# MCU.net
KiCad netlist of a schematic drawn in Altium Designer
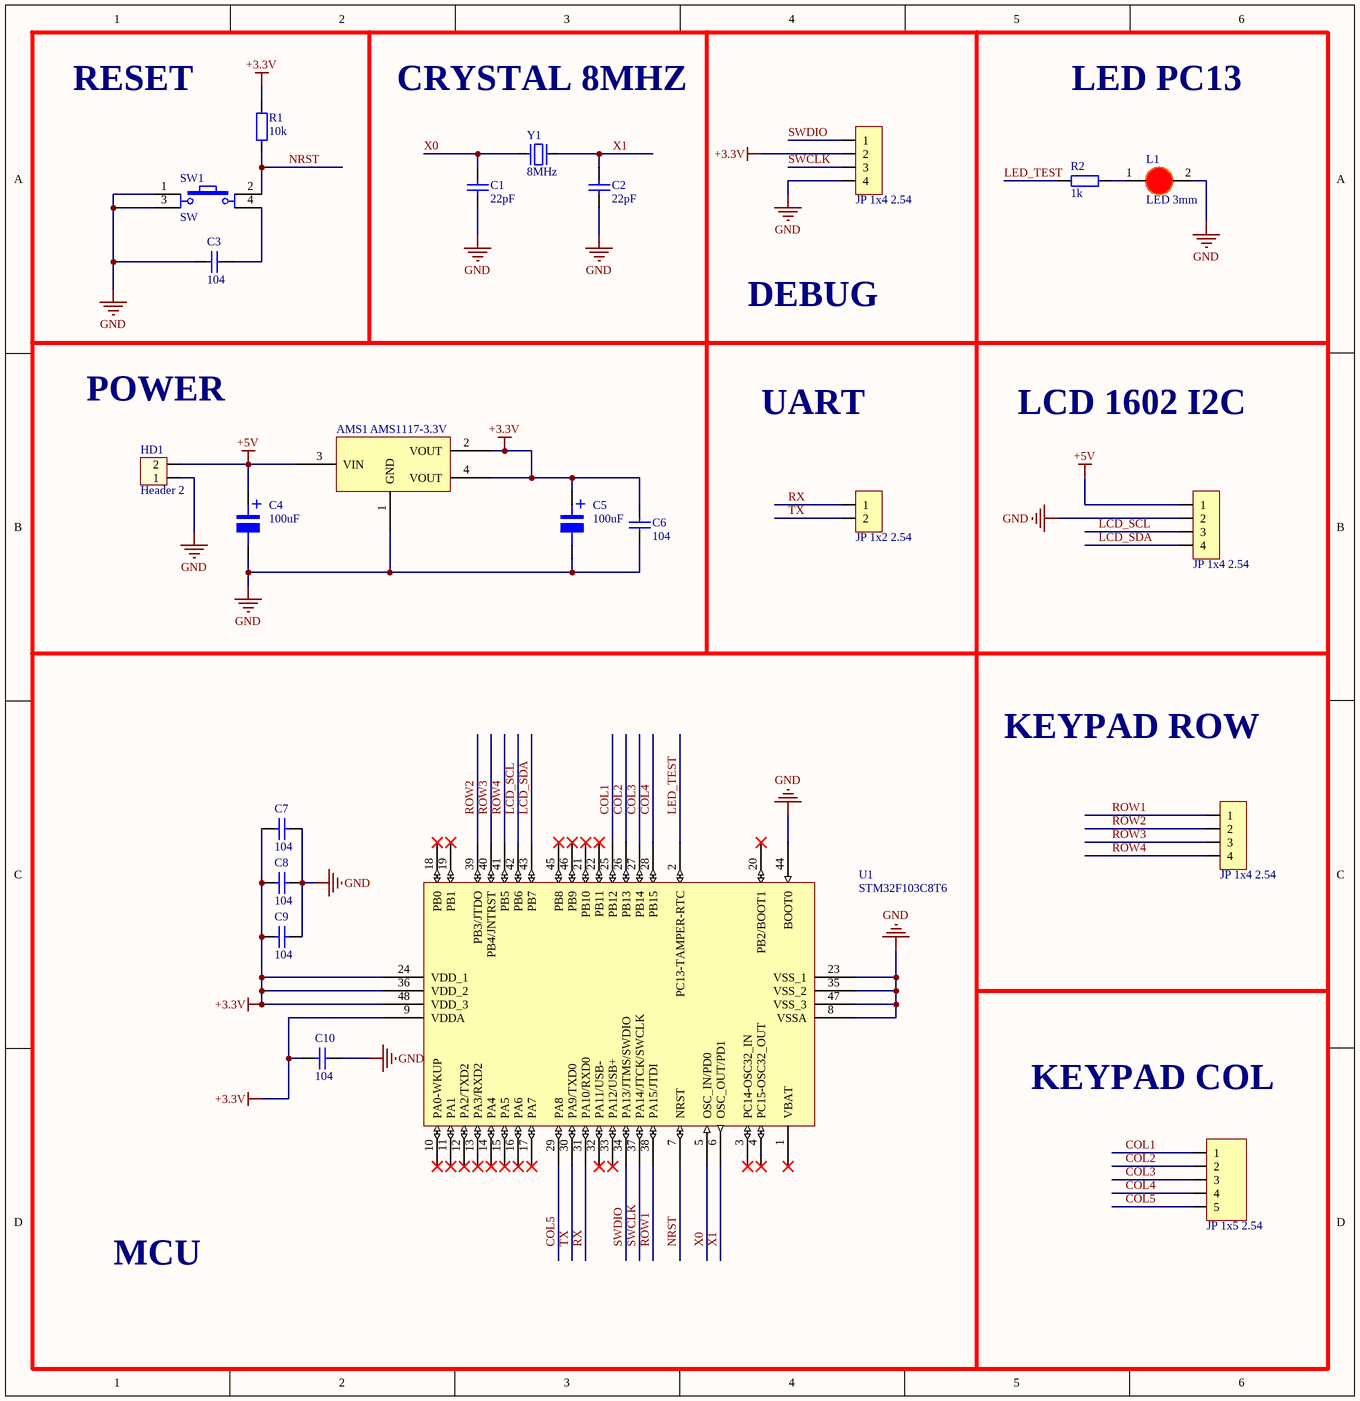
[diagram p0: MCU.SchDoc]

(export (version "E")
  (design (tool "Eeschema 10.0.6"))
  (components
    (comp (ref "AMS1")
      (value "AMS1117-3.3V")
      (footprint "SOT223")
      (description "Dán")
      (libsource (lib "Altium_Lib_by_KhueNguyenCreator") (part "AMS1117 SMD"))
    )
    (comp (ref "C1")
      (value "22pF")
      (footprint "tu 1206")
      (description "Dán")
      (libsource (lib "Altium_Lib_by_KhueNguyenCreator") (part "Tu 1206 22pF 50V 10%"))
    )
    (comp (ref "C2")
      (value "22pF")
      (footprint "tu 1206")
      (description "Dán")
      (libsource (lib "Altium_Lib_by_KhueNguyenCreator") (part "Tu 1206 22pF 50V 10%"))
    )
    (comp (ref "C3")
      (value "104")
      (footprint "tu 1206")
      (description "Dán")
      (libsource (lib "Altium_Lib_by_KhueNguyenCreator") (part "Tu 1206 104 50V 20%"))
    )
    (comp (ref "C4")
      (value "100uF")
      (footprint "tu nhom 6.3 (d)")
      (description "Dán")
      (libsource (lib "Altium_Lib_by_KhueNguyenCreator") (part "Tu Nhom 100uF 16V"))
    )
    (comp (ref "C5")
      (value "100uF")
      (footprint "tu nhom 6.3 (d)")
      (description "Dán")
      (libsource (lib "Altium_Lib_by_KhueNguyenCreator") (part "Tu Nhom 100uF 16V"))
    )
    (comp (ref "C6")
      (value "104")
      (footprint "tu 1206")
      (description "Dán")
      (libsource (lib "Altium_Lib_by_KhueNguyenCreator") (part "Tu 1206 104 50V 20%"))
    )
    (comp (ref "C7")
      (value "104")
      (footprint "tu 1206")
      (description "Dán")
      (libsource (lib "Altium_Lib_by_KhueNguyenCreator") (part "Tu 1206 104 50V 20%"))
    )
    (comp (ref "C8")
      (value "104")
      (footprint "tu 1206")
      (description "Dán")
      (libsource (lib "Altium_Lib_by_KhueNguyenCreator") (part "Tu 1206 104 50V 20%"))
    )
    (comp (ref "C9")
      (value "104")
      (footprint "tu 1206")
      (description "Dán")
      (libsource (lib "Altium_Lib_by_KhueNguyenCreator") (part "Tu 1206 104 50V 20%"))
    )
    (comp (ref "C10")
      (value "104")
      (footprint "tu 1206")
      (description "Dán")
      (libsource (lib "Altium_Lib_by_KhueNguyenCreator") (part "Tu 1206 104 50V 20%"))
    )
    (comp (ref "HD1")
      (value "Header 2")
      (footprint "HED2")
      (description "Header 2 (Green)")
      (libsource (lib "syhaunguyen") (part "Hed2"))
    )
    (comp (ref "JP1")
      (value "JP 1x4 2.54")
      (footprint "JP 1x4 DT")
      (description "Cắm")
      (libsource (lib "Altium_Lib_by_KhueNguyenCreator") (part "JP 1x4 2.54 Duc Thang"))
    )
    (comp (ref "JP2")
      (value "JP 1x2 2.54")
      (footprint "JP 1x2 DT")
      (description "Cắm")
      (libsource (lib "Altium_Lib_by_KhueNguyenCreator") (part "JP 1x2 2.54 Duc Thang"))
    )
    (comp (ref "JP3")
      (value "JP 1x4 2.54")
      (footprint "JP 1x4 DT")
      (description "Cắm")
      (libsource (lib "Altium_Lib_by_KhueNguyenCreator") (part "JP 1x4 2.54 Duc Thang"))
    )
    (comp (ref "JP4")
      (value "JP 1x4 2.54")
      (footprint "JP 1x4 DT")
      (description "Cắm")
      (libsource (lib "Altium_Lib_by_KhueNguyenCreator") (part "JP 1x4 2.54 Duc Thang"))
    )
    (comp (ref "JP5")
      (value "JP 1x5 2.54")
      (footprint "JP 1x5 DT")
      (description "Cắm")
      (libsource (lib "Altium_Lib_by_KhueNguyenCreator") (part "JP 1x5 2.54 Duc Thang"))
    )
    (comp (ref "L1")
      (value "LED 3mm")
      (footprint "LED-3MM-RED")
      (description "Cắm")
      (libsource (lib "Altium_Lib_by_KhueNguyenCreator") (part "LED 3mm Do"))
    )
    (comp (ref "R1")
      (value "10k")
      (footprint "tro smd 1206")
      (description "Dán")
      (libsource (lib "Altium_Lib_by_KhueNguyenCreator") (part "Tro 1206 1% 10k"))
    )
    (comp (ref "R2")
      (value "1k")
      (footprint "tro smd 1206")
      (description "Dán")
      (libsource (lib "Altium_Lib_by_KhueNguyenCreator") (part "Tro 1206 1% 1k"))
    )
    (comp (ref "SW1")
      (value "SW")
      (footprint "SW4")
      (description "Switch button 4 pin")
      (libsource (lib "syhaunguyen") (part "SW4"))
    )
    (comp (ref "U1")
      (value "STM32F103C8T6")
      (footprint "LQFP48")
      (fields (field (name "PUBLISHER") "Altium Limited"))
      (libsource (lib "Electronic4u") (part "STM32F103C8T6"))
    )
    (comp (ref "Y1")
      (value "8MHz")
      (footprint "Thach Anh 2 chan SMD")
      (description "Crystal For all Crystal 2pin.")
      (libsource (lib "Altium_Lib_by_KhueNguyenCreator") (part "Thach Anh 2 chan SMD"))
    )
  )
  (nets
    (net (code "1") (name "+3.3V") (class "Default")
      (node (ref "AMS1") (pin "2") (pinfunction "VOUT_2") (pintype "passive"))
      (node (ref "AMS1") (pin "4") (pinfunction "VOUT_4") (pintype "passive"))
      (node (ref "C10") (pin "1") (pinfunction "1_1") (pintype "passive"))
      (node (ref "C5") (pin "1") (pinfunction "1_1") (pintype "passive"))
      (node (ref "C6") (pin "1") (pinfunction "1_1") (pintype "passive"))
      (node (ref "C7") (pin "1") (pinfunction "1_1") (pintype "passive"))
      (node (ref "C8") (pin "1") (pinfunction "1_1") (pintype "passive"))
      (node (ref "C9") (pin "1") (pinfunction "1_1") (pintype "passive"))
      (node (ref "JP1") (pin "2") (pinfunction "2_2") (pintype "passive"))
      (node (ref "R1") (pin "2") (pinfunction "2_2") (pintype "passive"))
      (node (ref "U1") (pin "24") (pinfunction "VDD_1_24") (pintype "power_in"))
      (node (ref "U1") (pin "36") (pinfunction "VDD_2_36") (pintype "power_in"))
      (node (ref "U1") (pin "48") (pinfunction "VDD_3_48") (pintype "power_in"))
      (node (ref "U1") (pin "9") (pinfunction "VDDA_9") (pintype "power_in"))
    )
    (net (code "2") (name "+5V") (class "Default")
      (node (ref "AMS1") (pin "3") (pinfunction "VIN_3") (pintype "passive"))
      (node (ref "C4") (pin "1") (pinfunction "1_1") (pintype "passive"))
      (node (ref "HD1") (pin "2") (pinfunction "2_2") (pintype "passive"))
      (node (ref "JP3") (pin "1") (pinfunction "1_1") (pintype "passive"))
    )
    (net (code "3") (name "/COL1") (class "Default")
      (node (ref "JP5") (pin "1") (pinfunction "1_1") (pintype "passive"))
      (node (ref "U1") (pin "25") (pinfunction "PB12_25") (pintype "bidirectional"))
    )
    (net (code "4") (name "/COL2") (class "Default")
      (node (ref "JP5") (pin "2") (pinfunction "2_2") (pintype "passive"))
      (node (ref "U1") (pin "26") (pinfunction "PB13_26") (pintype "bidirectional"))
    )
    (net (code "5") (name "/COL3") (class "Default")
      (node (ref "JP5") (pin "3") (pinfunction "3_3") (pintype "passive"))
      (node (ref "U1") (pin "27") (pinfunction "PB14_27") (pintype "bidirectional"))
    )
    (net (code "6") (name "/COL4") (class "Default")
      (node (ref "JP5") (pin "4") (pinfunction "4_4") (pintype "passive"))
      (node (ref "U1") (pin "28") (pinfunction "PB15_28") (pintype "bidirectional"))
    )
    (net (code "7") (name "/COL5") (class "Default")
      (node (ref "JP5") (pin "5") (pinfunction "5_5") (pintype "passive"))
      (node (ref "U1") (pin "29") (pinfunction "PA8_29") (pintype "bidirectional"))
    )
    (net (code "8") (name "/LCD_SCL") (class "Default")
      (node (ref "JP3") (pin "3") (pinfunction "3_3") (pintype "passive"))
      (node (ref "U1") (pin "42") (pinfunction "PB6_42") (pintype "bidirectional"))
    )
    (net (code "9") (name "/LCD_SDA") (class "Default")
      (node (ref "JP3") (pin "4") (pinfunction "4_4") (pintype "passive"))
      (node (ref "U1") (pin "43") (pinfunction "PB7_43") (pintype "bidirectional"))
    )
    (net (code "10") (name "/LED_TEST") (class "Default")
      (node (ref "R2") (pin "1") (pinfunction "1_1") (pintype "passive"))
      (node (ref "U1") (pin "2") (pinfunction "PC13-TAMPER-RTC_2") (pintype "bidirectional"))
    )
    (net (code "11") (name "/NRST") (class "Default")
      (node (ref "R1") (pin "1") (pinfunction "1_1") (pintype "passive"))
      (node (ref "SW1") (pin "2") (pintype "passive"))
      (node (ref "U1") (pin "7") (pinfunction "NRST_7") (pintype "bidirectional"))
    )
    (net (code "12") (name "/ROW1") (class "Default")
      (node (ref "JP4") (pin "1") (pinfunction "1_1") (pintype "passive"))
      (node (ref "U1") (pin "38") (pinfunction "PA15/JTDI_38") (pintype "bidirectional"))
    )
    (net (code "13") (name "/ROW2") (class "Default")
      (node (ref "JP4") (pin "2") (pinfunction "2_2") (pintype "passive"))
      (node (ref "U1") (pin "39") (pinfunction "PB3/JTDO_39") (pintype "bidirectional"))
    )
    (net (code "14") (name "/ROW3") (class "Default")
      (node (ref "JP4") (pin "3") (pinfunction "3_3") (pintype "passive"))
      (node (ref "U1") (pin "40") (pinfunction "PB4/JNTRST_40") (pintype "bidirectional"))
    )
    (net (code "15") (name "/ROW4") (class "Default")
      (node (ref "JP4") (pin "4") (pinfunction "4_4") (pintype "passive"))
      (node (ref "U1") (pin "41") (pinfunction "PB5_41") (pintype "bidirectional"))
    )
    (net (code "16") (name "/RX") (class "Default")
      (node (ref "JP2") (pin "1") (pinfunction "1_1") (pintype "passive"))
      (node (ref "U1") (pin "31") (pinfunction "PA10/RXD0_31") (pintype "bidirectional"))
    )
    (net (code "17") (name "/SWCLK") (class "Default")
      (node (ref "JP1") (pin "3") (pinfunction "3_3") (pintype "passive"))
      (node (ref "U1") (pin "37") (pinfunction "PA14/JTCK/SWCLK_37") (pintype "bidirectional"))
    )
    (net (code "18") (name "/SWDIO") (class "Default")
      (node (ref "JP1") (pin "1") (pinfunction "1_1") (pintype "passive"))
      (node (ref "U1") (pin "34") (pinfunction "PA13/JTMS/SWDIO_34") (pintype "bidirectional"))
    )
    (net (code "19") (name "/TX") (class "Default")
      (node (ref "JP2") (pin "2") (pinfunction "2_2") (pintype "passive"))
      (node (ref "U1") (pin "30") (pinfunction "PA9/TXD0_30") (pintype "bidirectional"))
    )
    (net (code "20") (name "/X0") (class "Default")
      (node (ref "C1") (pin "1") (pinfunction "1_1") (pintype "passive"))
      (node (ref "U1") (pin "5") (pinfunction "OSC_IN/PD0_5") (pintype "input"))
      (node (ref "Y1") (pin "1") (pinfunction "1_1") (pintype "passive"))
    )
    (net (code "21") (name "/X1") (class "Default")
      (node (ref "C2") (pin "1") (pinfunction "1_1") (pintype "passive"))
      (node (ref "U1") (pin "6") (pinfunction "OSC_OUT/PD1_6") (pintype "output"))
      (node (ref "Y1") (pin "2") (pinfunction "2_2") (pintype "passive"))
    )
    (net (code "22") (name "GND") (class "Default")
      (node (ref "AMS1") (pin "1") (pinfunction "GND_1") (pintype "passive"))
      (node (ref "C1") (pin "2") (pinfunction "2_2") (pintype "passive"))
      (node (ref "C10") (pin "2") (pinfunction "2_2") (pintype "passive"))
      (node (ref "C2") (pin "2") (pinfunction "2_2") (pintype "passive"))
      (node (ref "C3") (pin "1") (pinfunction "1_1") (pintype "passive"))
      (node (ref "C4") (pin "2") (pinfunction "2_2") (pintype "passive"))
      (node (ref "C5") (pin "2") (pinfunction "2_2") (pintype "passive"))
      (node (ref "C6") (pin "2") (pinfunction "2_2") (pintype "passive"))
      (node (ref "C7") (pin "2") (pinfunction "2_2") (pintype "passive"))
      (node (ref "C8") (pin "2") (pinfunction "2_2") (pintype "passive"))
      (node (ref "C9") (pin "2") (pinfunction "2_2") (pintype "passive"))
      (node (ref "HD1") (pin "1") (pinfunction "1_1") (pintype "passive"))
      (node (ref "JP1") (pin "4") (pinfunction "4_4") (pintype "passive"))
      (node (ref "JP3") (pin "2") (pinfunction "2_2") (pintype "passive"))
      (node (ref "L1") (pin "2") (pinfunction "K_2") (pintype "passive"))
      (node (ref "SW1") (pin "1") (pintype "passive"))
      (node (ref "SW1") (pin "3") (pintype "passive"))
      (node (ref "U1") (pin "23") (pinfunction "VSS_1_23") (pintype "power_in"))
      (node (ref "U1") (pin "35") (pinfunction "VSS_2_35") (pintype "power_in"))
      (node (ref "U1") (pin "44") (pinfunction "BOOT0_44") (pintype "input"))
      (node (ref "U1") (pin "47") (pinfunction "VSS_3_47") (pintype "power_in"))
      (node (ref "U1") (pin "8") (pinfunction "VSSA_8") (pintype "power_in"))
    )
    (net (code "23") (name "Net-(C3-Pad2)") (class "Default")
      (node (ref "C3") (pin "2") (pinfunction "2_2") (pintype "passive"))
      (node (ref "SW1") (pin "4") (pintype "passive"))
    )
    (net (code "24") (name "Net-(L1-A)") (class "Default")
      (node (ref "L1") (pin "1") (pinfunction "A_1") (pintype "passive"))
      (node (ref "R2") (pin "2") (pinfunction "2_2") (pintype "passive"))
    )
    (net (code "25") (name "unconnected-(U1-PA0-WKUP-Pad10)") (class "Default")
      (node (ref "U1") (pin "10") (pinfunction "PA0-WKUP_10") (pintype "bidirectional+no_connect"))
    )
    (net (code "26") (name "unconnected-(U1-PA1-Pad11)") (class "Default")
      (node (ref "U1") (pin "11") (pinfunction "PA1_11") (pintype "bidirectional+no_connect"))
    )
    (net (code "27") (name "unconnected-(U1-PA2{slash}TXD2-Pad12)") (class "Default")
      (node (ref "U1") (pin "12") (pinfunction "PA2/TXD2_12") (pintype "bidirectional+no_connect"))
    )
    (net (code "28") (name "unconnected-(U1-PA3{slash}RXD2-Pad13)") (class "Default")
      (node (ref "U1") (pin "13") (pinfunction "PA3/RXD2_13") (pintype "bidirectional+no_connect"))
    )
    (net (code "29") (name "unconnected-(U1-PA4-Pad14)") (class "Default")
      (node (ref "U1") (pin "14") (pinfunction "PA4_14") (pintype "bidirectional+no_connect"))
    )
    (net (code "30") (name "unconnected-(U1-PA5-Pad15)") (class "Default")
      (node (ref "U1") (pin "15") (pinfunction "PA5_15") (pintype "bidirectional+no_connect"))
    )
    (net (code "31") (name "unconnected-(U1-PA6-Pad16)") (class "Default")
      (node (ref "U1") (pin "16") (pinfunction "PA6_16") (pintype "bidirectional+no_connect"))
    )
    (net (code "32") (name "unconnected-(U1-PA7-Pad17)") (class "Default")
      (node (ref "U1") (pin "17") (pinfunction "PA7_17") (pintype "bidirectional+no_connect"))
    )
    (net (code "33") (name "unconnected-(U1-PA11{slash}USB--Pad32)") (class "Default")
      (node (ref "U1") (pin "32") (pinfunction "PA11/USB-_32") (pintype "bidirectional+no_connect"))
    )
    (net (code "34") (name "unconnected-(U1-PA12{slash}USB+-Pad33)") (class "Default")
      (node (ref "U1") (pin "33") (pinfunction "PA12/USB+_33") (pintype "bidirectional+no_connect"))
    )
    (net (code "35") (name "unconnected-(U1-PB0-Pad18)") (class "Default")
      (node (ref "U1") (pin "18") (pinfunction "PB0_18") (pintype "bidirectional+no_connect"))
    )
    (net (code "36") (name "unconnected-(U1-PB1-Pad19)") (class "Default")
      (node (ref "U1") (pin "19") (pinfunction "PB1_19") (pintype "bidirectional+no_connect"))
    )
    (net (code "37") (name "unconnected-(U1-PB2{slash}BOOT1-Pad20)") (class "Default")
      (node (ref "U1") (pin "20") (pinfunction "PB2/BOOT1_20") (pintype "bidirectional+no_connect"))
    )
    (net (code "38") (name "unconnected-(U1-PB8-Pad45)") (class "Default")
      (node (ref "U1") (pin "45") (pinfunction "PB8_45") (pintype "bidirectional+no_connect"))
    )
    (net (code "39") (name "unconnected-(U1-PB9-Pad46)") (class "Default")
      (node (ref "U1") (pin "46") (pinfunction "PB9_46") (pintype "bidirectional+no_connect"))
    )
    (net (code "40") (name "unconnected-(U1-PB10-Pad21)") (class "Default")
      (node (ref "U1") (pin "21") (pinfunction "PB10_21") (pintype "bidirectional+no_connect"))
    )
    (net (code "41") (name "unconnected-(U1-PB11-Pad22)") (class "Default")
      (node (ref "U1") (pin "22") (pinfunction "PB11_22") (pintype "bidirectional+no_connect"))
    )
    (net (code "42") (name "unconnected-(U1-PC14-OSC32_IN-Pad3)") (class "Default")
      (node (ref "U1") (pin "3") (pinfunction "PC14-OSC32_IN_3") (pintype "bidirectional+no_connect"))
    )
    (net (code "43") (name "unconnected-(U1-PC15-OSC32_OUT-Pad4)") (class "Default")
      (node (ref "U1") (pin "4") (pinfunction "PC15-OSC32_OUT_4") (pintype "bidirectional+no_connect"))
    )
    (net (code "44") (name "unconnected-(U1-VBAT-Pad1)") (class "Default")
      (node (ref "U1") (pin "1") (pinfunction "VBAT_1") (pintype "power_in+no_connect"))
    )
  )
)
